# Qt_Py_j-link.net
KiCad netlist of a schematic drawn in EAGLE
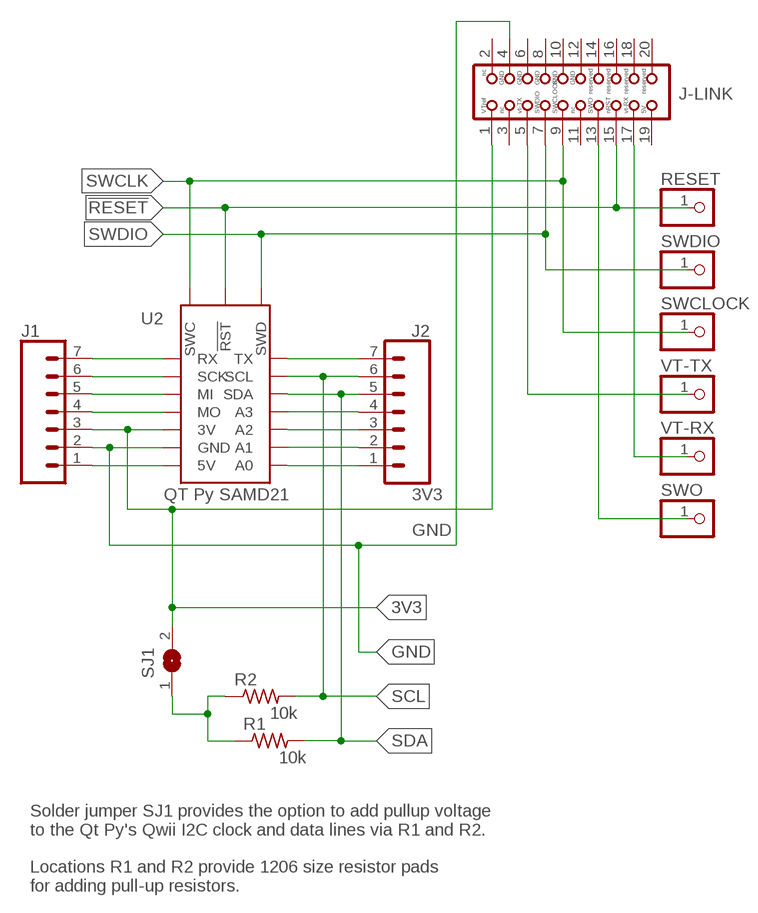
[diagram p0: schematic, sheet 1]

(export (version "E")
  (design (tool "Eeschema 10.0.6"))
  (components
    (comp (ref "J-LINK")
      (value "JLINK-ARM")
      (footprint "eagle-import:JTAG-ARM")
      (libsource (lib "eagle-import") (part "JLINK-ARM"))
    )
    (comp (ref "J1")
      (value "CONN_07")
      (footprint "eagle-import:1X07")
      (libsource (lib "eagle-import") (part "CONN_07"))
    )
    (comp (ref "J2")
      (value "CONN_07")
      (footprint "eagle-import:1X07")
      (libsource (lib "eagle-import") (part "CONN_07"))
    )
    (comp (ref "R1")
      (value "10k")
      (footprint "eagle-import:M1206")
      (libsource (lib "eagle-import") (part "R-US_M1206"))
    )
    (comp (ref "R2")
      (value "10k")
      (footprint "eagle-import:M1206")
      (libsource (lib "eagle-import") (part "R-US_M1206"))
    )
    (comp (ref "RESET")
      (value "PINHD-1X1")
      (footprint "eagle-import:1X01")
      (libsource (lib "eagle-import") (part "PINHD-1X1"))
    )
    (comp (ref "SJ1")
      (value "SJ-OPEN")
      (footprint "eagle-import:SJ")
      (libsource (lib "eagle-import") (part "SJ-OPEN"))
    )
    (comp (ref "SWCLOCK")
      (value "PINHD-1X1")
      (footprint "eagle-import:1X01")
      (libsource (lib "eagle-import") (part "PINHD-1X1"))
    )
    (comp (ref "SWDIO")
      (value "PINHD-1X1")
      (footprint "eagle-import:1X01")
      (libsource (lib "eagle-import") (part "PINHD-1X1"))
    )
    (comp (ref "SWO")
      (value "PINHD-1X1")
      (footprint "eagle-import:1X01")
      (libsource (lib "eagle-import") (part "PINHD-1X1"))
    )
    (comp (ref "U2")
      (value "QT Py SAMD21")
      (footprint "eagle-import:QT_PY-SWD-TH")
      (libsource (lib "eagle-import") (part "QT_PY-SWD-TH"))
    )
    (comp (ref "VT-RX")
      (value "PINHD-1X1")
      (footprint "eagle-import:1X01")
      (libsource (lib "eagle-import") (part "PINHD-1X1"))
    )
    (comp (ref "VT-TX")
      (value "PINHD-1X1")
      (footprint "eagle-import:1X01")
      (libsource (lib "eagle-import") (part "PINHD-1X1"))
    )
  )
  (nets
    (net (code "1") (name "/~{RESET}") (class "Default")
      (node (ref "J-LINK") (pin "15") (pinfunction "15_15") (pintype "passive"))
      (node (ref "RESET") (pin "1") (pinfunction "1_1") (pintype "passive"))
      (node (ref "U2") (pin "!RESET") (pinfunction "~{RST}_!RESET") (pintype "bidirectional"))
    )
    (net (code "2") (name "3V3") (class "Default")
      (node (ref "J-LINK") (pin "1") (pinfunction "1_1") (pintype "passive"))
      (node (ref "J1") (pin "3") (pinfunction "3_3") (pintype "passive"))
      (node (ref "SJ1") (pin "2") (pinfunction "2_2") (pintype "passive"))
      (node (ref "U2") (pin "3V3@1") (pinfunction "3V_3V3@1") (pintype "power_in"))
      (node (ref "U2") (pin "3V3@2") (pinfunction "3V_3V3@2") (pintype "power_in"))
    )
    (net (code "3") (name "GND") (class "Default")
      (node (ref "J-LINK") (pin "4") (pinfunction "4_4") (pintype "passive"))
      (node (ref "J1") (pin "2") (pinfunction "2_2") (pintype "passive"))
      (node (ref "U2") (pin "GND@1") (pinfunction "GND_GND@1") (pintype "power_in"))
      (node (ref "U2") (pin "GND@2") (pinfunction "GND_GND@2") (pintype "power_in"))
    )
    (net (code "4") (name "Net-(J-LINK-Pad5)") (class "Default")
      (node (ref "J-LINK") (pin "5") (pinfunction "5_5") (pintype "passive"))
      (node (ref "VT-TX") (pin "1") (pinfunction "1_1") (pintype "passive"))
    )
    (net (code "5") (name "Net-(J-LINK-Pad13)") (class "Default")
      (node (ref "J-LINK") (pin "13") (pinfunction "13_13") (pintype "passive"))
      (node (ref "SWO") (pin "1") (pinfunction "1_1") (pintype "passive"))
    )
    (net (code "6") (name "Net-(J-LINK-Pad17)") (class "Default")
      (node (ref "J-LINK") (pin "17") (pinfunction "17_17") (pintype "passive"))
      (node (ref "VT-RX") (pin "1") (pinfunction "1_1") (pintype "passive"))
    )
    (net (code "7") (name "Net-(J1-Pad1)") (class "Default")
      (node (ref "J1") (pin "1") (pinfunction "1_1") (pintype "passive"))
      (node (ref "U2") (pin "5V@1") (pinfunction "5V_5V@1") (pintype "power_in"))
      (node (ref "U2") (pin "5V@2") (pinfunction "5V_5V@2") (pintype "power_in"))
    )
    (net (code "8") (name "Net-(J1-Pad4)") (class "Default")
      (node (ref "J1") (pin "4") (pinfunction "4_4") (pintype "passive"))
      (node (ref "U2") (pin "MOSI@1") (pinfunction "MO_MOSI@1") (pintype "bidirectional"))
      (node (ref "U2") (pin "MOSI@2") (pinfunction "MO_MOSI@2") (pintype "bidirectional"))
    )
    (net (code "9") (name "Net-(J1-Pad5)") (class "Default")
      (node (ref "J1") (pin "5") (pinfunction "5_5") (pintype "passive"))
      (node (ref "U2") (pin "MISO@1") (pinfunction "MI_MISO@1") (pintype "bidirectional"))
      (node (ref "U2") (pin "MISO@2") (pinfunction "MI_MISO@2") (pintype "bidirectional"))
    )
    (net (code "10") (name "Net-(J1-Pad6)") (class "Default")
      (node (ref "J1") (pin "6") (pinfunction "6_6") (pintype "passive"))
      (node (ref "U2") (pin "SCLK@1") (pinfunction "SCK_SCLK@1") (pintype "bidirectional"))
      (node (ref "U2") (pin "SCLK@2") (pinfunction "SCK_SCLK@2") (pintype "bidirectional"))
    )
    (net (code "11") (name "Net-(J1-Pad7)") (class "Default")
      (node (ref "J1") (pin "7") (pinfunction "7_7") (pintype "passive"))
      (node (ref "U2") (pin "RX@1") (pinfunction "RX_RX@1") (pintype "bidirectional"))
      (node (ref "U2") (pin "RX@2") (pinfunction "RX_RX@2") (pintype "bidirectional"))
    )
    (net (code "12") (name "Net-(J2-Pad1)") (class "Default")
      (node (ref "J2") (pin "1") (pinfunction "1_1") (pintype "passive"))
      (node (ref "U2") (pin "A0@1") (pinfunction "A0_A0@1") (pintype "bidirectional"))
      (node (ref "U2") (pin "A0@2") (pinfunction "A0_A0@2") (pintype "bidirectional"))
    )
    (net (code "13") (name "Net-(J2-Pad2)") (class "Default")
      (node (ref "J2") (pin "2") (pinfunction "2_2") (pintype "passive"))
      (node (ref "U2") (pin "A1@1") (pinfunction "A1_A1@1") (pintype "bidirectional"))
      (node (ref "U2") (pin "A1@2") (pinfunction "A1_A1@2") (pintype "bidirectional"))
    )
    (net (code "14") (name "Net-(J2-Pad3)") (class "Default")
      (node (ref "J2") (pin "3") (pinfunction "3_3") (pintype "passive"))
      (node (ref "U2") (pin "A2@1") (pinfunction "A2_A2@1") (pintype "bidirectional"))
      (node (ref "U2") (pin "A2@2") (pinfunction "A2_A2@2") (pintype "bidirectional"))
    )
    (net (code "15") (name "Net-(J2-Pad4)") (class "Default")
      (node (ref "J2") (pin "4") (pinfunction "4_4") (pintype "passive"))
      (node (ref "U2") (pin "A3@1") (pinfunction "A3_A3@1") (pintype "bidirectional"))
      (node (ref "U2") (pin "A3@2") (pinfunction "A3_A3@2") (pintype "bidirectional"))
    )
    (net (code "16") (name "Net-(J2-Pad7)") (class "Default")
      (node (ref "J2") (pin "7") (pinfunction "7_7") (pintype "passive"))
      (node (ref "U2") (pin "TX@1") (pinfunction "TX_TX@1") (pintype "bidirectional"))
      (node (ref "U2") (pin "TX@2") (pinfunction "TX_TX@2") (pintype "bidirectional"))
    )
    (net (code "17") (name "Net-(R1-Pad1)") (class "Default")
      (node (ref "R1") (pin "1") (pinfunction "1_1") (pintype "passive"))
      (node (ref "R2") (pin "1") (pinfunction "1_1") (pintype "passive"))
      (node (ref "SJ1") (pin "1") (pinfunction "1_1") (pintype "passive"))
    )
    (net (code "18") (name "SCL") (class "Default")
      (node (ref "J2") (pin "6") (pinfunction "6_6") (pintype "passive"))
      (node (ref "R2") (pin "2") (pinfunction "2_2") (pintype "passive"))
      (node (ref "U2") (pin "SCL@1") (pinfunction "SCL_SCL@1") (pintype "bidirectional"))
      (node (ref "U2") (pin "SCL@2") (pinfunction "SCL_SCL@2") (pintype "bidirectional"))
    )
    (net (code "19") (name "SDA") (class "Default")
      (node (ref "J2") (pin "5") (pinfunction "5_5") (pintype "passive"))
      (node (ref "R1") (pin "2") (pinfunction "2_2") (pintype "passive"))
      (node (ref "U2") (pin "SDA@1") (pinfunction "SDA_SDA@1") (pintype "bidirectional"))
      (node (ref "U2") (pin "SDA@2") (pinfunction "SDA_SDA@2") (pintype "bidirectional"))
    )
    (net (code "20") (name "SWCLK") (class "Default")
      (node (ref "J-LINK") (pin "9") (pinfunction "9_9") (pintype "passive"))
      (node (ref "SWCLOCK") (pin "1") (pinfunction "1_1") (pintype "passive"))
      (node (ref "U2") (pin "SWCLK") (pinfunction "SWC_SWCLK") (pintype "bidirectional"))
    )
    (net (code "21") (name "SWDIO") (class "Default")
      (node (ref "J-LINK") (pin "7") (pinfunction "7_7") (pintype "passive"))
      (node (ref "SWDIO") (pin "1") (pinfunction "1_1") (pintype "passive"))
      (node (ref "U2") (pin "SWDIO") (pinfunction "SWD_SWDIO") (pintype "bidirectional"))
    )
    (net (code "22") (name "unconnected-(J-LINK-Pad2)") (class "Default")
      (node (ref "J-LINK") (pin "2") (pinfunction "2_2") (pintype "passive"))
    )
    (net (code "23") (name "unconnected-(J-LINK-Pad3)") (class "Default")
      (node (ref "J-LINK") (pin "3") (pinfunction "3_3") (pintype "passive"))
    )
    (net (code "24") (name "unconnected-(J-LINK-Pad6)") (class "Default")
      (node (ref "J-LINK") (pin "6") (pinfunction "6_6") (pintype "passive"))
    )
    (net (code "25") (name "unconnected-(J-LINK-Pad8)") (class "Default")
      (node (ref "J-LINK") (pin "8") (pinfunction "8_8") (pintype "passive"))
    )
    (net (code "26") (name "unconnected-(J-LINK-Pad10)") (class "Default")
      (node (ref "J-LINK") (pin "10") (pinfunction "10_10") (pintype "passive"))
    )
    (net (code "27") (name "unconnected-(J-LINK-Pad11)") (class "Default")
      (node (ref "J-LINK") (pin "11") (pinfunction "11_11") (pintype "passive"))
    )
    (net (code "28") (name "unconnected-(J-LINK-Pad12)") (class "Default")
      (node (ref "J-LINK") (pin "12") (pinfunction "12_12") (pintype "passive"))
    )
    (net (code "29") (name "unconnected-(J-LINK-Pad14)") (class "Default")
      (node (ref "J-LINK") (pin "14") (pinfunction "14_14") (pintype "passive"))
    )
    (net (code "30") (name "unconnected-(J-LINK-Pad16)") (class "Default")
      (node (ref "J-LINK") (pin "16") (pinfunction "16_16") (pintype "passive"))
    )
    (net (code "31") (name "unconnected-(J-LINK-Pad18)") (class "Default")
      (node (ref "J-LINK") (pin "18") (pinfunction "18_18") (pintype "passive"))
    )
    (net (code "32") (name "unconnected-(J-LINK-Pad19)") (class "Default")
      (node (ref "J-LINK") (pin "19") (pinfunction "19_19") (pintype "passive"))
    )
    (net (code "33") (name "unconnected-(J-LINK-Pad20)") (class "Default")
      (node (ref "J-LINK") (pin "20") (pinfunction "20_20") (pintype "passive"))
    )
  )
)
